# obc_spi_to_i2c.net
KiCad netlist of a schematic drawn in Altium Designer
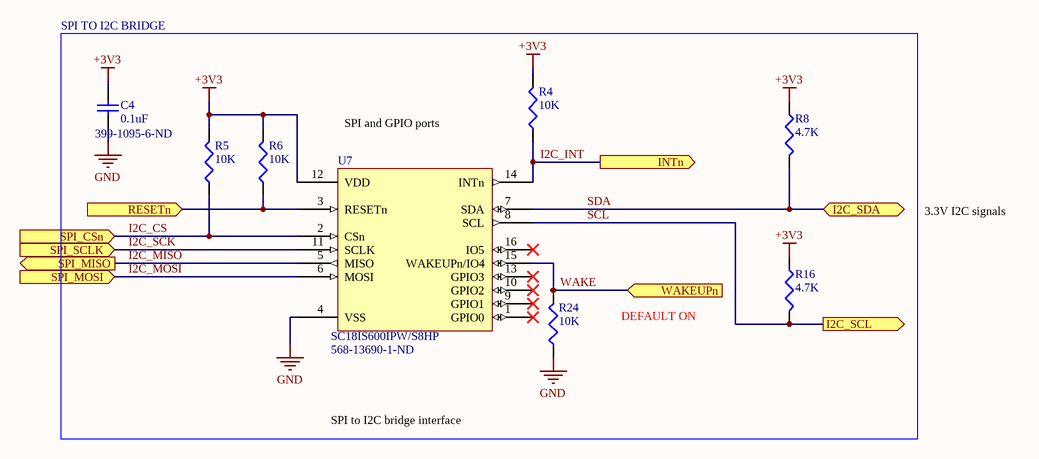
[diagram p0: obc_spi_to_i2c.SchDoc]

(export (version "E")
  (design (tool "Eeschema 10.0.6"))
  (components
    (comp (ref "C4")
      (value "0.1uF")
      (footprint "1608[0603]")
      (description "Capacitor")
      (fields
        (field (name "SUPPLIER PART NUMBER 1") "399-1095-6-ND")
        (field (name "PUBLISHER") "Altium Limited")
      )
      (libsource (lib "Miscellaneous Devices") (part "Cap"))
    )
    (comp (ref "R4")
      (value "10K")
      (footprint "J1-0603")
      (description "Resistor")
      (fields (field (name "PUBLISHER") "Altium Limited"))
      (libsource (lib "Miscellaneous Devices") (part "Res3"))
    )
    (comp (ref "R5")
      (value "10K")
      (footprint "J1-0603")
      (description "Resistor")
      (fields (field (name "PUBLISHER") "Altium Limited"))
      (libsource (lib "Miscellaneous Devices") (part "Res3"))
    )
    (comp (ref "R6")
      (value "10K")
      (footprint "J1-0603")
      (description "Resistor")
      (fields (field (name "PUBLISHER") "Altium Limited"))
      (libsource (lib "Miscellaneous Devices") (part "Res3"))
    )
    (comp (ref "R8")
      (value "4.7K")
      (footprint "J1-0603")
      (description "Resistor")
      (fields (field (name "PUBLISHER") "Altium Limited"))
      (libsource (lib "Miscellaneous Devices") (part "Res3"))
    )
    (comp (ref "R16")
      (value "4.7K")
      (footprint "J1-0603")
      (description "Resistor")
      (fields (field (name "PUBLISHER") "Altium Limited"))
      (libsource (lib "Miscellaneous Devices") (part "Res3"))
    )
    (comp (ref "R24")
      (value "10K")
      (footprint "J1-0603")
      (description "Resistor")
      (fields (field (name "PUBLISHER") "Altium Limited"))
      (libsource (lib "Miscellaneous Devices") (part "Res3"))
    )
    (comp (ref "U7")
      (value "SC18IS600IPW/S8HP")
      (footprint "TSOP65P640X110-16N")
      (description "SPI to I2C bridge.")
      (fields (field (name "SUPPLIER PART NUMBER 1") "568-13690-1-ND"))
      (libsource (lib "ICs") (part "SC18IS600IPW/S8HP"))
    )
  )
  (nets
    (net (code "1") (name "+3V3") (class "Default")
      (node (ref "C4") (pin "2") (pinfunction "2_2") (pintype "passive"))
      (node (ref "R16") (pin "1") (pinfunction "1_1") (pintype "passive"))
      (node (ref "R4") (pin "2") (pinfunction "2_2") (pintype "passive"))
      (node (ref "R5") (pin "2") (pinfunction "2_2") (pintype "passive"))
      (node (ref "R6") (pin "2") (pinfunction "2_2") (pintype "passive"))
      (node (ref "R8") (pin "1") (pinfunction "1_1") (pintype "passive"))
      (node (ref "U7") (pin "12") (pinfunction "VDD_12") (pintype "power_in"))
    )
    (net (code "2") (name "/I2C_CS") (class "Default")
      (node (ref "R5") (pin "1") (pinfunction "1_1") (pintype "passive"))
      (node (ref "U7") (pin "2") (pinfunction "CSn_2") (pintype "input"))
    )
    (net (code "3") (name "/I2C_INT") (class "Default")
      (node (ref "R4") (pin "1") (pinfunction "1_1") (pintype "passive"))
      (node (ref "U7") (pin "14") (pinfunction "INTn_14") (pintype "output"))
    )
    (net (code "4") (name "/I2C_MISO") (class "Default")
      (node (ref "U7") (pin "5") (pinfunction "MISO_5") (pintype "output"))
    )
    (net (code "5") (name "/I2C_MOSI") (class "Default")
      (node (ref "U7") (pin "6") (pinfunction "MOSI_6") (pintype "input"))
    )
    (net (code "6") (name "/I2C_SCK") (class "Default")
      (node (ref "U7") (pin "11") (pinfunction "SCLK_11") (pintype "input"))
    )
    (net (code "7") (name "/RESETn") (class "Default")
      (node (ref "R6") (pin "1") (pinfunction "1_1") (pintype "passive"))
      (node (ref "U7") (pin "3") (pinfunction "RESETn_3") (pintype "input"))
    )
    (net (code "8") (name "/SCL") (class "Default")
      (node (ref "R16") (pin "2") (pinfunction "2_2") (pintype "passive"))
      (node (ref "U7") (pin "8") (pinfunction "SCL_8") (pintype "output"))
    )
    (net (code "9") (name "/SDA") (class "Default")
      (node (ref "R8") (pin "2") (pinfunction "2_2") (pintype "passive"))
      (node (ref "U7") (pin "7") (pinfunction "SDA_7") (pintype "bidirectional"))
    )
    (net (code "10") (name "/WAKE") (class "Default")
      (node (ref "R24") (pin "2") (pinfunction "2_2") (pintype "passive"))
      (node (ref "U7") (pin "15") (pinfunction "WAKEUPn/IO4_15") (pintype "bidirectional"))
    )
    (net (code "11") (name "GND") (class "Default")
      (node (ref "C4") (pin "1") (pinfunction "1_1") (pintype "passive"))
      (node (ref "R24") (pin "1") (pinfunction "1_1") (pintype "passive"))
      (node (ref "U7") (pin "4") (pinfunction "VSS_4") (pintype "power_in"))
    )
    (net (code "12") (name "unconnected-(U7-GPIO0-Pad1)") (class "Default")
      (node (ref "U7") (pin "1") (pinfunction "GPIO0_1") (pintype "bidirectional+no_connect"))
    )
    (net (code "13") (name "unconnected-(U7-GPIO1-Pad9)") (class "Default")
      (node (ref "U7") (pin "9") (pinfunction "GPIO1_9") (pintype "bidirectional+no_connect"))
    )
    (net (code "14") (name "unconnected-(U7-GPIO2-Pad10)") (class "Default")
      (node (ref "U7") (pin "10") (pinfunction "GPIO2_10") (pintype "bidirectional+no_connect"))
    )
    (net (code "15") (name "unconnected-(U7-GPIO3-Pad13)") (class "Default")
      (node (ref "U7") (pin "13") (pinfunction "GPIO3_13") (pintype "bidirectional+no_connect"))
    )
    (net (code "16") (name "unconnected-(U7-IO5-Pad16)") (class "Default")
      (node (ref "U7") (pin "16") (pinfunction "IO5_16") (pintype "bidirectional+no_connect"))
    )
  )
)
